# design.net
KiCad netlist of a schematic drawn in EasyEDA Pro
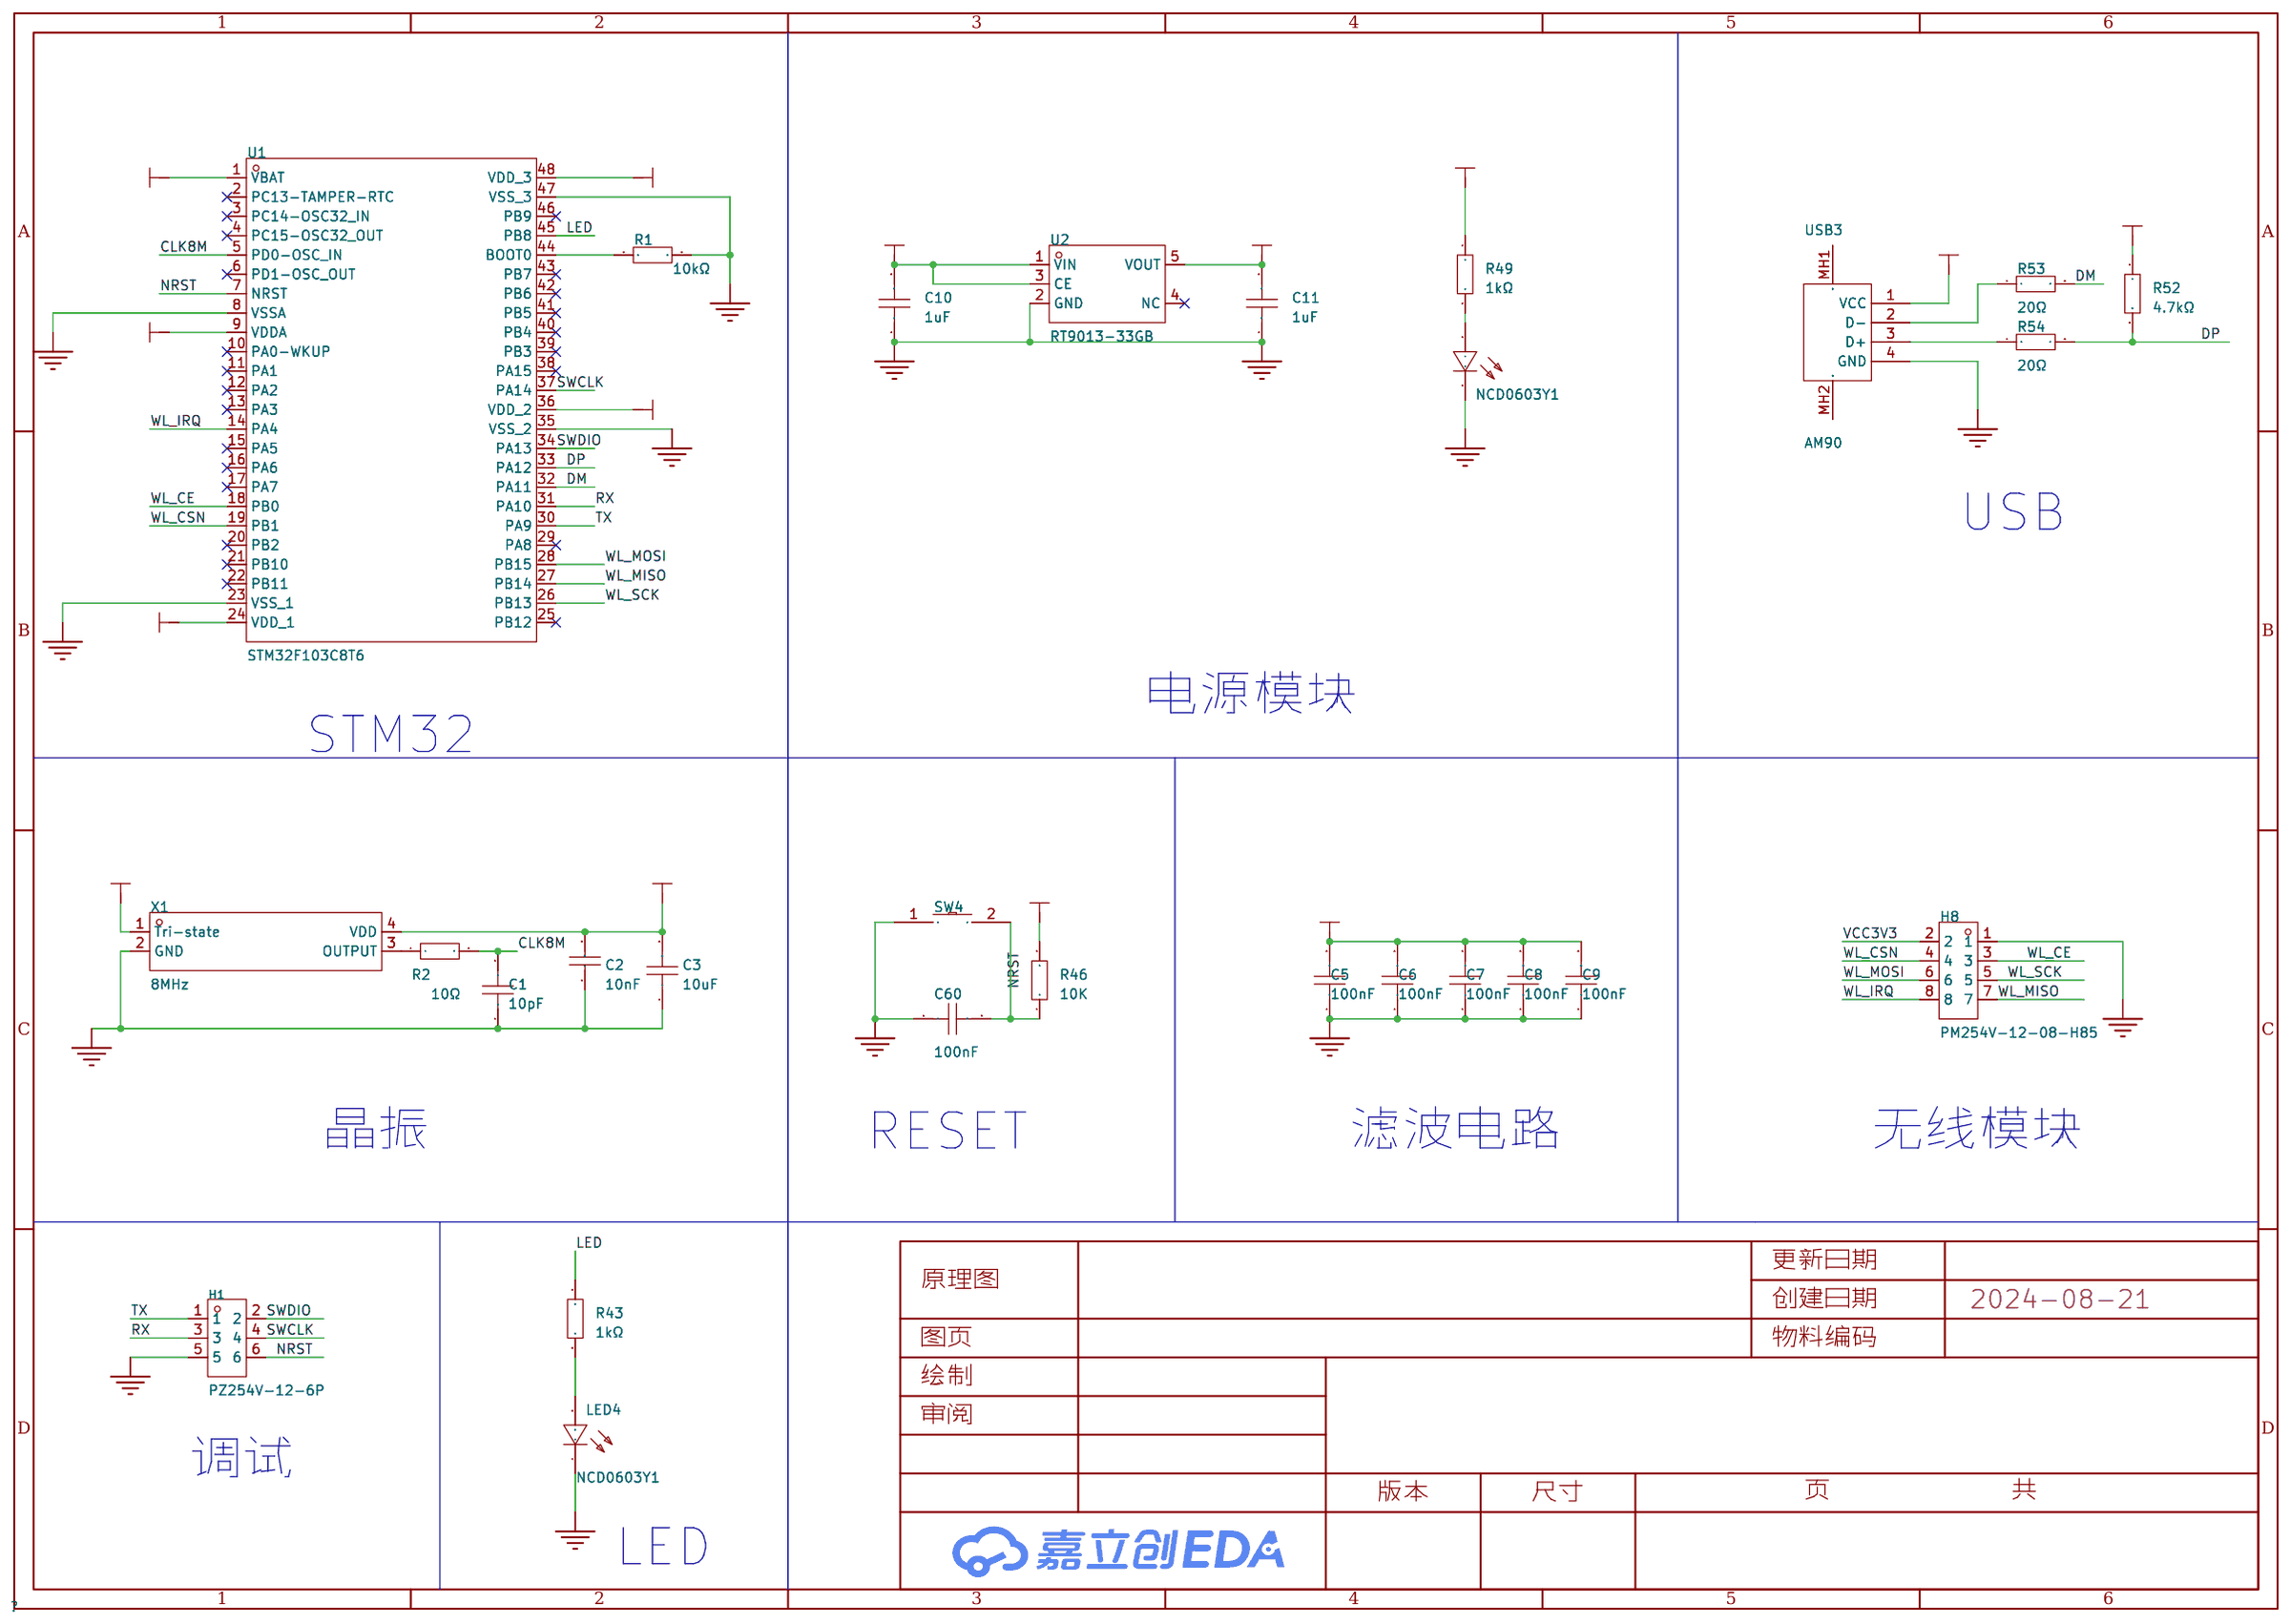
[diagram p0: schematic sheet]

(export (version "E")
  (design (tool "Eeschema 10.0.6"))
  (components
    (comp (ref "C1")
      (value "10pF")
      (footprint "easyedapro:C0603")
      (description "容值:10pF;精度:±5%;额定电压:50V;材质(温度系数):C0G;")
      (fields (field (name "Manufacturer Part") "0603CG100J500NT") (field (name "Manufacturer") "FH(风华)"))
      (libsource (lib "easyedapro") (part "0603CG100J500NT"))
    )
    (comp (ref "C2")
      (value "10nF")
      (footprint "easyedapro:C0603")
      (description "容值:10nF;精度:±10%;额定电压:50V;材质(温度系数):X7R;")
      (fields (field (name "Manufacturer Part") "0603B103K500NT") (field (name "Manufacturer") "FH(风华)"))
      (libsource (lib "easyedapro") (part "0603B103K500NT"))
    )
    (comp (ref "C3")
      (value "10uF")
      (footprint "easyedapro:C0603")
      (description "容值:10uF;精度:±10%;额定电压:10V;材质(温度系数):X5R;")
      (fields
        (field (name "Manufacturer Part") "CL10A106KP8NNNC")
        (field (name "Manufacturer") "SAMSUNG(三星)")
      )
      (libsource (lib "easyedapro") (part "CL10A106KP8NNNC"))
    )
    (comp (ref "C5")
      (value "100nF")
      (footprint "easyedapro:C0603")
      (description "容值:100nF;精度:±10%;额定电压:50V;材质(温度系数):X7R;")
      (fields
        (field (name "Manufacturer Part") "CC0603KRX7R9BB104")
        (field (name "Manufacturer") "YAGEO(国巨)")
      )
      (libsource (lib "easyedapro") (part "CC0603KRX7R9BB104"))
    )
    (comp (ref "C6")
      (value "100nF")
      (footprint "easyedapro:C0603")
      (description "容值:100nF;精度:±10%;额定电压:50V;材质(温度系数):X7R;")
      (fields
        (field (name "Manufacturer Part") "CC0603KRX7R9BB104")
        (field (name "Manufacturer") "YAGEO(国巨)")
      )
      (libsource (lib "easyedapro") (part "CC0603KRX7R9BB104"))
    )
    (comp (ref "C7")
      (value "100nF")
      (footprint "easyedapro:C0603")
      (description "容值:100nF;精度:±10%;额定电压:50V;材质(温度系数):X7R;")
      (fields
        (field (name "Manufacturer Part") "CC0603KRX7R9BB104")
        (field (name "Manufacturer") "YAGEO(国巨)")
      )
      (libsource (lib "easyedapro") (part "CC0603KRX7R9BB104"))
    )
    (comp (ref "C8")
      (value "100nF")
      (footprint "easyedapro:C0603")
      (description "容值:100nF;精度:±10%;额定电压:50V;材质(温度系数):X7R;")
      (fields
        (field (name "Manufacturer Part") "CC0603KRX7R9BB104")
        (field (name "Manufacturer") "YAGEO(国巨)")
      )
      (libsource (lib "easyedapro") (part "CC0603KRX7R9BB104"))
    )
    (comp (ref "C9")
      (value "100nF")
      (footprint "easyedapro:C0603")
      (description "容值:100nF;精度:±10%;额定电压:50V;材质(温度系数):X7R;")
      (fields
        (field (name "Manufacturer Part") "CC0603KRX7R9BB104")
        (field (name "Manufacturer") "YAGEO(国巨)")
      )
      (libsource (lib "easyedapro") (part "CC0603KRX7R9BB104"))
    )
    (comp (ref "C10")
      (value "1uF")
      (footprint "easyedapro:C0603")
      (description "容值:1uF;精度:±10%;额定电压:50V;材质(温度系数):X5R;")
      (fields
        (field (name "Manufacturer Part") "CL10A105KB8NNNC")
        (field (name "Manufacturer") "SAMSUNG(三星)")
      )
      (libsource (lib "easyedapro") (part "CL10A105KB8NNNC"))
    )
    (comp (ref "C11")
      (value "1uF")
      (footprint "easyedapro:C0603")
      (description "容值:1uF;精度:±10%;额定电压:50V;材质(温度系数):X5R;")
      (fields
        (field (name "Manufacturer Part") "CL10A105KB8NNNC")
        (field (name "Manufacturer") "SAMSUNG(三星)")
      )
      (libsource (lib "easyedapro") (part "CL10A105KB8NNNC"))
    )
    (comp (ref "C60")
      (value "100nF")
      (footprint "easyedapro:C0603")
      (libsource (lib "easyedapro") (part "CapAcitance"))
    )
    (comp (ref "H1")
      (value "PZ254V-12-6P")
      (fields (field (name "Manufacturer") "XFCN(兴飞)"))
      (libsource (lib "easyedapro") (part "PZ254V-12-6P"))
    )
    (comp (ref "H8")
      (value "PM254V-12-08-H85")
      (footprint "easyedapro:HDR-TH_8P-P2.54-V-F-R2-C4-S2.54")
      (fields (field (name "Manufacturer") "XFCN(兴飞)"))
      (libsource (lib "easyedapro") (part "PM254V-12-08-H85_C2834799"))
    )
    (comp (ref "LED4")
      (value "NCD0603Y1")
      (footprint "easyedapro:LED0603-RD")
      (description "发光颜色:黄色;功率:65mW;透镜颜色:无色透明;主波长:586nm~595nm;发光强度:80mcd~220mcd;发光角度:130°;工作温度:-30°C~+85°C;")
      (fields (field (name "Manufacturer") "国星光电"))
      (libsource (lib "easyedapro") (part "FC-D1608HYK-588J"))
    )
    (comp (ref "LED9")
      (value "NCD0603Y1")
      (footprint "easyedapro:LED0603-RD")
      (description "发光颜色:黄色;功率:65mW;透镜颜色:无色透明;主波长:586nm~595nm;发光强度:80mcd~220mcd;发光角度:130°;工作温度:-30°C~+85°C;")
      (fields (field (name "Manufacturer") "国星光电"))
      (libsource (lib "easyedapro") (part "FC-D1608HYK-588J"))
    )
    (comp (ref "R1")
      (value "10kΩ")
      (footprint "easyedapro:R0603")
      (description "电阻类型:厚膜电阻;阻值:10kΩ;精度:±1%;功率:100mW;最大工作电压:75V;温度系数:±100ppm/°C;")
      (fields
        (field (name "Manufacturer Part") "0603WAF1002T5E")
        (field (name "Manufacturer") "UNI-ROYAL(厚声)")
      )
      (libsource (lib "easyedapro") (part "0603WAF1002T5E"))
    )
    (comp (ref "R2")
      (value "10Ω")
      (footprint "easyedapro:R0603")
      (description "电阻类型:厚膜电阻;阻值:10Ω;精度:±1%;功率:100mW;最大工作电压:75V;温度系数:±400ppm/°C;")
      (fields
        (field (name "Manufacturer Part") "0603WAF100JT5E")
        (field (name "Manufacturer") "UNI-ROYAL(厚声)")
      )
      (libsource (lib "easyedapro") (part "0603WAF100JT5E"))
    )
    (comp (ref "R43")
      (value "1kΩ")
      (footprint "easyedapro:R0603")
      (description "电阻类型:厚膜电阻;阻值:1kΩ;精度:±1%;功率:100mW;最大工作电压:75V;温度系数:±100ppm/°C;")
      (fields
        (field (name "Manufacturer Part") "0603WAF1001T5E")
        (field (name "Manufacturer") "UNI-ROYAL(厚声)")
      )
      (libsource (lib "easyedapro") (part "0603WAF1001T5E"))
    )
    (comp (ref "R46") (value "10K") (footprint "easyedapro:R0603") (libsource (lib "easyedapro") (part "电阻")))
    (comp (ref "R49")
      (value "1kΩ")
      (footprint "easyedapro:R0603")
      (description "电阻类型:厚膜电阻;阻值:1kΩ;精度:±1%;功率:100mW;最大工作电压:75V;温度系数:±100ppm/°C;")
      (fields
        (field (name "Manufacturer Part") "0603WAF1001T5E")
        (field (name "Manufacturer") "UNI-ROYAL(厚声)")
      )
      (libsource (lib "easyedapro") (part "0603WAF1001T5E"))
    )
    (comp (ref "R52")
      (value "4.7kΩ")
      (footprint "easyedapro:R0603")
      (description "电阻类型:厚膜电阻;阻值:4.7kΩ;精度:±1%;功率:100mW;最大工作电压:75V;温度系数:±100ppm/°C;")
      (fields (field (name "Manufacturer Part") "RC0603FR-074K7L") (field (name "Manufacturer") "YAGEO(国巨)"))
      (libsource (lib "easyedapro") (part "RC0603FR-074K7L"))
    )
    (comp (ref "R53")
      (value "20Ω")
      (footprint "easyedapro:R0603")
      (description "电阻类型:厚膜电阻;阻值:20Ω;精度:±1%;功率:100mW;最大工作电压:75V;温度系数:±100ppm/°C;")
      (fields
        (field (name "Manufacturer Part") "0603WAF200JT5E")
        (field (name "Manufacturer") "UNI-ROYAL(厚声)")
      )
      (libsource (lib "easyedapro") (part "0603WAF200JT5E"))
    )
    (comp (ref "R54")
      (value "20Ω")
      (footprint "easyedapro:R0603")
      (description "电阻类型:厚膜电阻;阻值:20Ω;精度:±1%;功率:100mW;最大工作电压:75V;温度系数:±100ppm/°C;")
      (fields
        (field (name "Manufacturer Part") "0603WAF200JT5E")
        (field (name "Manufacturer") "UNI-ROYAL(厚声)")
      )
      (libsource (lib "easyedapro") (part "0603WAF200JT5E"))
    )
    (comp (ref "SW4")
      (value "TS-1101-C-W")
      (footprint "easyedapro:SW-SMD_L6.0-W3.3-LS8.0")
      (fields (field (name "Manufacturer") "XKB Connectivity(中国星坤)"))
      (libsource (lib "easyedapro") (part "TS-1101-C-W"))
    )
    (comp (ref "U1")
      (value "STM32F103C8T6")
      (footprint "easyedapro:LQFP-48_L7.0-W7.0-P0.50-LS9.0-BL")
      (fields (field (name "Manufacturer") "ST(意法半导体)"))
      (libsource (lib "easyedapro") (part "STM32F103C8T6"))
    )
    (comp (ref "U2")
      (value "RT9013-33GB")
      (footprint "easyedapro:SOT-23-5_L2.9-W1.6-P0.95-LS2.8-BR")
      (fields (field (name "Manufacturer") "TECH PUBLIC(台舟)"))
      (libsource (lib "easyedapro") (part "RT9013-33GB_C19268157"))
    )
    (comp (ref "USB3")
      (value "AM90")
      (footprint "easyedapro:USB-AM-TH_AM90")
      (description "连接器类型:Type-A;标准:USB 2.0;公母:公;端口数量:1;触点数量:4P;安装方式:弯插;额定电流 - 电源:-;工作温度范围:-;")
      (fields (field (name "Manufacturer") "SHOU HAN(首韩)"))
      (libsource (lib "easyedapro") (part "AM90"))
    )
    (comp (ref "X1")
      (value "8MHz")
      (footprint "easyedapro:OSC-SMD_4P-L3.2-W2.5-BL_SIT8008BI")
      (description "频率:8MHz;工作电压:3.3V;输出模式:CMOS;频率稳定度:±20ppm;")
      (fields
        (field (name "Manufacturer Part") "S3D8.000000B20F30T")
        (field (name "Manufacturer") "SCTF(星通时频)")
      )
      (libsource (lib "easyedapro") (part "S3D8.000000B20F30T"))
    )
  )
  (nets
    (net (code "1") (name "/CLK8M") (class "Default")
      (node (ref "C1") (pin "2") (pinfunction "2_2") (pintype "unspecified"))
      (node (ref "R2") (pin "2") (pinfunction "2_2") (pintype "input"))
      (node (ref "U1") (pin "5") (pinfunction "PD0-OSC_IN_5") (pintype "unspecified"))
    )
    (net (code "2") (name "/DM") (class "Default")
      (node (ref "R53") (pin "2") (pinfunction "2_2") (pintype "input"))
      (node (ref "U1") (pin "32") (pinfunction "PA11_32") (pintype "unspecified"))
    )
    (net (code "3") (name "/DP") (class "Default")
      (node (ref "R52") (pin "2") (pinfunction "2_2") (pintype "input"))
      (node (ref "R54") (pin "2") (pinfunction "2_2") (pintype "input"))
      (node (ref "U1") (pin "33") (pinfunction "PA12_33") (pintype "unspecified"))
    )
    (net (code "4") (name "/LED") (class "Default")
      (node (ref "R43") (pin "1") (pinfunction "1_1") (pintype "input"))
      (node (ref "U1") (pin "45") (pinfunction "PB8_45") (pintype "unspecified"))
    )
    (net (code "5") (name "/NRST") (class "Default")
      (node (ref "C60") (pin "2") (pinfunction "2_2") (pintype "input"))
      (node (ref "H1") (pin "6") (pinfunction "6_6") (pintype "input"))
      (node (ref "R46") (pin "1") (pinfunction "1_1") (pintype "input"))
      (node (ref "SW4") (pin "2") (pinfunction "2_2") (pintype "unspecified"))
      (node (ref "U1") (pin "7") (pinfunction "NRST_7") (pintype "unspecified"))
    )
    (net (code "6") (name "/RX") (class "Default")
      (node (ref "H1") (pin "3") (pinfunction "3_3") (pintype "input"))
      (node (ref "U1") (pin "31") (pinfunction "PA10_31") (pintype "unspecified"))
    )
    (net (code "7") (name "/SWCLK") (class "Default")
      (node (ref "H1") (pin "4") (pinfunction "4_4") (pintype "input"))
      (node (ref "U1") (pin "37") (pinfunction "PA14_37") (pintype "unspecified"))
    )
    (net (code "8") (name "/SWDIO") (class "Default")
      (node (ref "H1") (pin "2") (pinfunction "2_2") (pintype "input"))
      (node (ref "U1") (pin "34") (pinfunction "PA13_34") (pintype "unspecified"))
    )
    (net (code "9") (name "/TX") (class "Default")
      (node (ref "H1") (pin "1") (pinfunction "1_1") (pintype "input"))
      (node (ref "U1") (pin "30") (pinfunction "PA9_30") (pintype "unspecified"))
    )
    (net (code "10") (name "/WL_CE") (class "Default")
      (node (ref "H8") (pin "3") (pinfunction "3_3") (pintype "unspecified"))
      (node (ref "U1") (pin "18") (pinfunction "PB0_18") (pintype "unspecified"))
    )
    (net (code "11") (name "/WL_CSN") (class "Default")
      (node (ref "H8") (pin "4") (pinfunction "4_4") (pintype "unspecified"))
      (node (ref "U1") (pin "19") (pinfunction "PB1_19") (pintype "unspecified"))
    )
    (net (code "12") (name "/WL_IRQ") (class "Default")
      (node (ref "H8") (pin "8") (pinfunction "8_8") (pintype "unspecified"))
      (node (ref "U1") (pin "14") (pinfunction "PA4_14") (pintype "unspecified"))
    )
    (net (code "13") (name "/WL_MISO") (class "Default")
      (node (ref "H8") (pin "7") (pinfunction "7_7") (pintype "unspecified"))
      (node (ref "U1") (pin "27") (pinfunction "PB14_27") (pintype "unspecified"))
    )
    (net (code "14") (name "/WL_MOSI") (class "Default")
      (node (ref "H8") (pin "6") (pinfunction "6_6") (pintype "unspecified"))
      (node (ref "U1") (pin "28") (pinfunction "PB15_28") (pintype "unspecified"))
    )
    (net (code "15") (name "/WL_SCK") (class "Default")
      (node (ref "H8") (pin "5") (pinfunction "5_5") (pintype "unspecified"))
      (node (ref "U1") (pin "26") (pinfunction "PB13_26") (pintype "unspecified"))
    )
    (net (code "16") (name "GND") (class "Default")
      (node (ref "C1") (pin "1") (pinfunction "1_1") (pintype "unspecified"))
      (node (ref "C10") (pin "1") (pinfunction "1_1") (pintype "unspecified"))
      (node (ref "C11") (pin "1") (pinfunction "1_1") (pintype "unspecified"))
      (node (ref "C2") (pin "1") (pinfunction "1_1") (pintype "input"))
      (node (ref "C3") (pin "1") (pinfunction "1_1") (pintype "unspecified"))
      (node (ref "C5") (pin "1") (pinfunction "1_1") (pintype "unspecified"))
      (node (ref "C6") (pin "1") (pinfunction "1_1") (pintype "unspecified"))
      (node (ref "C60") (pin "1") (pinfunction "1_1") (pintype "input"))
      (node (ref "C7") (pin "1") (pinfunction "1_1") (pintype "unspecified"))
      (node (ref "C8") (pin "1") (pinfunction "1_1") (pintype "unspecified"))
      (node (ref "C9") (pin "1") (pinfunction "1_1") (pintype "unspecified"))
      (node (ref "H1") (pin "5") (pinfunction "5_5") (pintype "input"))
      (node (ref "H8") (pin "1") (pinfunction "1_1") (pintype "unspecified"))
      (node (ref "LED4") (pin "1") (pinfunction "K_1") (pintype "input"))
      (node (ref "LED9") (pin "1") (pinfunction "K_1") (pintype "input"))
      (node (ref "R1") (pin "2") (pinfunction "2_2") (pintype "input"))
      (node (ref "SW4") (pin "1") (pinfunction "1_1") (pintype "unspecified"))
      (node (ref "U1") (pin "23") (pinfunction "VSS_1_23") (pintype "unspecified"))
      (node (ref "U1") (pin "35") (pinfunction "VSS_2_35") (pintype "unspecified"))
      (node (ref "U1") (pin "47") (pinfunction "VSS_3_47") (pintype "unspecified"))
      (node (ref "U1") (pin "8") (pinfunction "VSSA_8") (pintype "unspecified"))
      (node (ref "U2") (pin "2") (pinfunction "GND_2") (pintype "unspecified"))
      (node (ref "USB3") (pin "4") (pinfunction "GND_4") (pintype "input"))
      (node (ref "X1") (pin "2") (pinfunction "GND_2") (pintype "unspecified"))
    )
    (net (code "17") (name "Net-(LED4-A)") (class "Default")
      (node (ref "LED4") (pin "2") (pinfunction "A_2") (pintype "input"))
      (node (ref "R43") (pin "2") (pinfunction "2_2") (pintype "input"))
    )
    (net (code "18") (name "Net-(LED9-A)") (class "Default")
      (node (ref "LED9") (pin "2") (pinfunction "A_2") (pintype "input"))
      (node (ref "R49") (pin "2") (pinfunction "2_2") (pintype "input"))
    )
    (net (code "19") (name "Net-(U1-BOOT0)") (class "Default")
      (node (ref "R1") (pin "1") (pinfunction "1_1") (pintype "input"))
      (node (ref "U1") (pin "44") (pinfunction "BOOT0_44") (pintype "unspecified"))
    )
    (net (code "20") (name "Net-(USB3-D+)") (class "Default")
      (node (ref "R54") (pin "1") (pinfunction "1_1") (pintype "input"))
      (node (ref "USB3") (pin "3") (pinfunction "D+_3") (pintype "input"))
    )
    (net (code "21") (name "Net-(USB3-D-)") (class "Default")
      (node (ref "R53") (pin "1") (pinfunction "1_1") (pintype "input"))
      (node (ref "USB3") (pin "2") (pinfunction "D-_2") (pintype "input"))
    )
    (net (code "22") (name "Net-(X1-OUTPUT)") (class "Default")
      (node (ref "R2") (pin "1") (pinfunction "1_1") (pintype "input"))
      (node (ref "X1") (pin "3") (pinfunction "OUTPUT_3") (pintype "unspecified"))
    )
    (net (code "23") (name "PIVCC5V") (class "Default")
      (node (ref "C10") (pin "2") (pinfunction "2_2") (pintype "unspecified"))
      (node (ref "R52") (pin "1") (pinfunction "1_1") (pintype "input"))
      (node (ref "U2") (pin "1") (pinfunction "VIN_1") (pintype "unspecified"))
      (node (ref "U2") (pin "3") (pinfunction "CE_3") (pintype "unspecified"))
      (node (ref "USB3") (pin "1") (pinfunction "VCC_1") (pintype "input"))
    )
    (net (code "24") (name "VCC3V3") (class "Default")
      (node (ref "C11") (pin "2") (pinfunction "2_2") (pintype "unspecified"))
      (node (ref "C2") (pin "2") (pinfunction "2_2") (pintype "input"))
      (node (ref "C3") (pin "2") (pinfunction "2_2") (pintype "unspecified"))
      (node (ref "C5") (pin "2") (pinfunction "2_2") (pintype "unspecified"))
      (node (ref "C6") (pin "2") (pinfunction "2_2") (pintype "unspecified"))
      (node (ref "C7") (pin "2") (pinfunction "2_2") (pintype "unspecified"))
      (node (ref "C8") (pin "2") (pinfunction "2_2") (pintype "unspecified"))
      (node (ref "C9") (pin "2") (pinfunction "2_2") (pintype "unspecified"))
      (node (ref "H8") (pin "2") (pinfunction "2_2") (pintype "unspecified"))
      (node (ref "R46") (pin "2") (pinfunction "2_2") (pintype "input"))
      (node (ref "R49") (pin "1") (pinfunction "1_1") (pintype "input"))
      (node (ref "U1") (pin "1") (pinfunction "VBAT_1") (pintype "unspecified"))
      (node (ref "U1") (pin "24") (pinfunction "VDD_1_24") (pintype "unspecified"))
      (node (ref "U1") (pin "36") (pinfunction "VDD_2_36") (pintype "unspecified"))
      (node (ref "U1") (pin "48") (pinfunction "VDD_3_48") (pintype "unspecified"))
      (node (ref "U1") (pin "9") (pinfunction "VDDA_9") (pintype "unspecified"))
      (node (ref "U2") (pin "5") (pinfunction "VOUT_5") (pintype "unspecified"))
      (node (ref "X1") (pin "1") (pinfunction "Tri-state_1") (pintype "unspecified"))
      (node (ref "X1") (pin "4") (pinfunction "VDD_4") (pintype "unspecified"))
    )
    (net (code "25") (name "unconnected-(U1-PA0-WKUP-Pad10)") (class "Default")
      (node (ref "U1") (pin "10") (pinfunction "PA0-WKUP_10") (pintype "unspecified+no_connect"))
    )
    (net (code "26") (name "unconnected-(U1-PA1-Pad11)") (class "Default")
      (node (ref "U1") (pin "11") (pinfunction "PA1_11") (pintype "unspecified+no_connect"))
    )
    (net (code "27") (name "unconnected-(U1-PA2-Pad12)") (class "Default")
      (node (ref "U1") (pin "12") (pinfunction "PA2_12") (pintype "unspecified+no_connect"))
    )
    (net (code "28") (name "unconnected-(U1-PA3-Pad13)") (class "Default")
      (node (ref "U1") (pin "13") (pinfunction "PA3_13") (pintype "unspecified+no_connect"))
    )
    (net (code "29") (name "unconnected-(U1-PA5-Pad15)") (class "Default")
      (node (ref "U1") (pin "15") (pinfunction "PA5_15") (pintype "unspecified+no_connect"))
    )
    (net (code "30") (name "unconnected-(U1-PA6-Pad16)") (class "Default")
      (node (ref "U1") (pin "16") (pinfunction "PA6_16") (pintype "unspecified+no_connect"))
    )
    (net (code "31") (name "unconnected-(U1-PA7-Pad17)") (class "Default")
      (node (ref "U1") (pin "17") (pinfunction "PA7_17") (pintype "unspecified+no_connect"))
    )
    (net (code "32") (name "unconnected-(U1-PA8-Pad29)") (class "Default")
      (node (ref "U1") (pin "29") (pinfunction "PA8_29") (pintype "unspecified+no_connect"))
    )
    (net (code "33") (name "unconnected-(U1-PA15-Pad38)") (class "Default")
      (node (ref "U1") (pin "38") (pinfunction "PA15_38") (pintype "unspecified+no_connect"))
    )
    (net (code "34") (name "unconnected-(U1-PB2-Pad20)") (class "Default")
      (node (ref "U1") (pin "20") (pinfunction "PB2_20") (pintype "unspecified+no_connect"))
    )
    (net (code "35") (name "unconnected-(U1-PB3-Pad39)") (class "Default")
      (node (ref "U1") (pin "39") (pinfunction "PB3_39") (pintype "unspecified+no_connect"))
    )
    (net (code "36") (name "unconnected-(U1-PB4-Pad40)") (class "Default")
      (node (ref "U1") (pin "40") (pinfunction "PB4_40") (pintype "unspecified+no_connect"))
    )
    (net (code "37") (name "unconnected-(U1-PB5-Pad41)") (class "Default")
      (node (ref "U1") (pin "41") (pinfunction "PB5_41") (pintype "unspecified+no_connect"))
    )
    (net (code "38") (name "unconnected-(U1-PB6-Pad42)") (class "Default")
      (node (ref "U1") (pin "42") (pinfunction "PB6_42") (pintype "unspecified+no_connect"))
    )
    (net (code "39") (name "unconnected-(U1-PB7-Pad43)") (class "Default")
      (node (ref "U1") (pin "43") (pinfunction "PB7_43") (pintype "unspecified+no_connect"))
    )
    (net (code "40") (name "unconnected-(U1-PB9-Pad46)") (class "Default")
      (node (ref "U1") (pin "46") (pinfunction "PB9_46") (pintype "unspecified+no_connect"))
    )
    (net (code "41") (name "unconnected-(U1-PB10-Pad21)") (class "Default")
      (node (ref "U1") (pin "21") (pinfunction "PB10_21") (pintype "unspecified+no_connect"))
    )
    (net (code "42") (name "unconnected-(U1-PB11-Pad22)") (class "Default")
      (node (ref "U1") (pin "22") (pinfunction "PB11_22") (pintype "unspecified+no_connect"))
    )
    (net (code "43") (name "unconnected-(U1-PB12-Pad25)") (class "Default")
      (node (ref "U1") (pin "25") (pinfunction "PB12_25") (pintype "unspecified+no_connect"))
    )
    (net (code "44") (name "unconnected-(U1-PC13-TAMPER-RTC-Pad2)") (class "Default")
      (node (ref "U1") (pin "2") (pinfunction "PC13-TAMPER-RTC_2") (pintype "unspecified+no_connect"))
    )
    (net (code "45") (name "unconnected-(U1-PC14-OSC32_IN-Pad3)") (class "Default")
      (node (ref "U1") (pin "3") (pinfunction "PC14-OSC32_IN_3") (pintype "unspecified+no_connect"))
    )
    (net (code "46") (name "unconnected-(U1-PC15-OSC32_OUT-Pad4)") (class "Default")
      (node (ref "U1") (pin "4") (pinfunction "PC15-OSC32_OUT_4") (pintype "unspecified+no_connect"))
    )
    (net (code "47") (name "unconnected-(U1-PD1-OSC_OUT-Pad6)") (class "Default")
      (node (ref "U1") (pin "6") (pinfunction "PD1-OSC_OUT_6") (pintype "unspecified+no_connect"))
    )
    (net (code "48") (name "unconnected-(U2-NC-Pad4)") (class "Default")
      (node (ref "U2") (pin "4") (pinfunction "NC_4") (pintype "unspecified+no_connect"))
    )
    (net (code "49") (name "unconnected-(USB3-PadMH1)") (class "Default")
      (node (ref "USB3") (pin "MH1") (pinfunction "MH1_MH1") (pintype "unspecified"))
    )
    (net (code "50") (name "unconnected-(USB3-PadMH2)") (class "Default")
      (node (ref "USB3") (pin "MH2") (pinfunction "MH2_MH2") (pintype "unspecified"))
    )
  )
)
